# OSCILLAR_HFB_V1p0_AGSB.net
KiCad netlist of a schematic drawn in Altium Designer
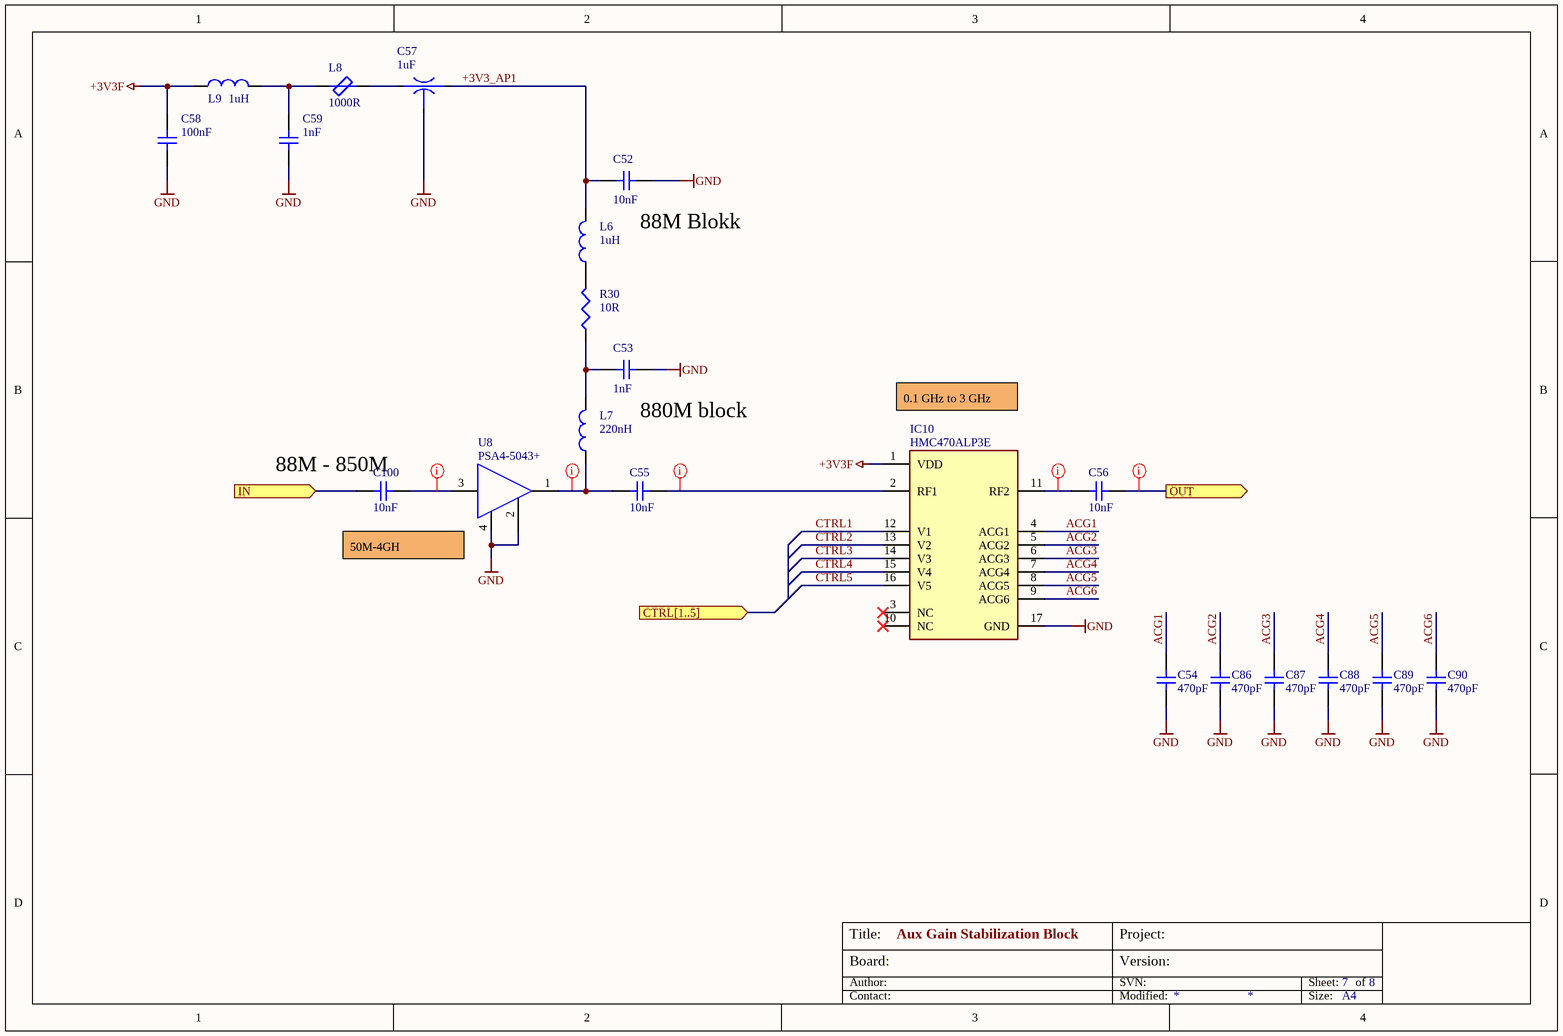
[diagram p0: OSCILLAR_HFB_V1p0_AGSB.SchDoc]

(export (version "E")
  (design (tool "Eeschema 10.0.6"))
  (components
    (comp (ref "C52")
      (value "10nF")
      (footprint "CAP-0805")
      (description "MLCC capacitor")
      (libsource (lib "SCHLIB") (part "NP-CAPACITOR"))
    )
    (comp (ref "C53")
      (value "1nF")
      (footprint "CAP-0805")
      (description "MLCC capacitor")
      (libsource (lib "SCHLIB") (part "NP-CAPACITOR"))
    )
    (comp (ref "C54")
      (value "470pF")
      (footprint "CAP_0603")
      (description "MLCC capacitor")
      (libsource (lib "SCHLIB") (part "NP-CAPACITOR"))
    )
    (comp (ref "C55")
      (value "10nF")
      (footprint "CAP_0603")
      (description "MLCC capacitor")
      (libsource (lib "SCHLIB") (part "NP-CAPACITOR"))
    )
    (comp (ref "C56")
      (value "10nF")
      (footprint "CAP_0603")
      (description "MLCC capacitor")
      (libsource (lib "SCHLIB") (part "NP-CAPACITOR"))
    )
    (comp (ref "C57")
      (value "1uF")
      (footprint "CAP-0805-EMI")
      (description "EMI filter capacitor")
      (libsource (lib "SCHLIB") (part "EMI_CAPACITOR"))
    )
    (comp (ref "C58")
      (value "100nF")
      (footprint "CAP-0805")
      (description "MLCC capacitor")
      (libsource (lib "SCHLIB") (part "NP-CAPACITOR"))
    )
    (comp (ref "C59")
      (value "1nF")
      (footprint "CAP-0805")
      (description "MLCC capacitor")
      (libsource (lib "SCHLIB") (part "NP-CAPACITOR"))
    )
    (comp (ref "C86")
      (value "470pF")
      (footprint "CAP_0603")
      (description "MLCC capacitor")
      (libsource (lib "SCHLIB") (part "NP-CAPACITOR"))
    )
    (comp (ref "C87")
      (value "470pF")
      (footprint "CAP_0603")
      (description "MLCC capacitor")
      (libsource (lib "SCHLIB") (part "NP-CAPACITOR"))
    )
    (comp (ref "C88")
      (value "470pF")
      (footprint "CAP_0603")
      (description "MLCC capacitor")
      (libsource (lib "SCHLIB") (part "NP-CAPACITOR"))
    )
    (comp (ref "C89")
      (value "470pF")
      (footprint "CAP_0603")
      (description "MLCC capacitor")
      (libsource (lib "SCHLIB") (part "NP-CAPACITOR"))
    )
    (comp (ref "C90")
      (value "470pF")
      (footprint "CAP_0603")
      (description "MLCC capacitor")
      (libsource (lib "SCHLIB") (part "NP-CAPACITOR"))
    )
    (comp (ref "C100")
      (value "10nF")
      (footprint "CAP_0603")
      (description "MLCC capacitor")
      (libsource (lib "SCHLIB") (part "NP-CAPACITOR"))
    )
    (comp (ref "IC10")
      (value "HMC470ALP3E")
      (footprint "QFN-16")
      (description "Attenuators 0.1 GHz to 3 GHz,1 dB LSB, 5-Bit, GaAs Digital Attenuator")
      (fields (field (name "PART NUMBER") "584-HMC470ALP3E"))
      (libsource (lib "SCHLIB") (part "HMC470ALP3E"))
    )
    (comp (ref "L6")
      (value "1uH")
      (footprint "IND-0805")
      (description "Air core coil")
      (libsource (lib "SCHLIB") (part "AC-INDUCTOR"))
    )
    (comp (ref "L7")
      (value "220nH")
      (footprint "IND-0805")
      (description "Air core coil")
      (libsource (lib "SCHLIB") (part "AC-INDUCTOR"))
    )
    (comp (ref "L8")
      (value "1000R")
      (footprint "IND-0805-EMI")
      (description "Chip Ferrite Bead, 1000R @100MHz, 1.6A")
      (fields (field (name "PART NUMBER") "81-BLM21SP102SN1D"))
      (libsource (lib "SCHLIB") (part "BLM21SP102SN1D"))
    )
    (comp (ref "L9")
      (value "1uH")
      (footprint "IND-0805-EMI")
      (description "Air core coil")
      (libsource (lib "SCHLIB") (part "AC-INDUCTOR"))
    )
    (comp (ref "R30")
      (value "10R")
      (footprint "RES-0805")
      (description "Metal Film Resistor")
      (libsource (lib "SCHLIB") (part "RESISTOR"))
    )
    (comp (ref "U8")
      (value "PSA4-5043+")
      (footprint "SOT-343-4")
      (description "RF Amplifier, Low noise, 50M-4GHz, +5V, +20dB")
      (fields (field (name "PART NUMBER") "139-PSA4-5043"))
      (libsource (lib "SCHLIB") (part "PSA4-5043+"))
    )
  )
  (nets
    (net (code "1") (name "+3V3F") (class "Default")
      (node (ref "C58") (pin "1") (pinfunction "1_1") (pintype "passive"))
      (node (ref "IC10") (pin "1") (pinfunction "VDD_1") (pintype "passive"))
      (node (ref "L9") (pin "1") (pinfunction "1_1") (pintype "passive"))
    )
    (net (code "2") (name "/+3V3_AP1") (class "Default")
      (node (ref "C52") (pin "1") (pinfunction "1_1") (pintype "passive"))
      (node (ref "C57") (pin "1") (pinfunction "1_1") (pintype "passive"))
      (node (ref "L6") (pin "2") (pinfunction "2_2") (pintype "passive"))
    )
    (net (code "3") (name "/ACG1") (class "Default")
      (node (ref "C54") (pin "1") (pinfunction "1_1") (pintype "passive"))
      (node (ref "IC10") (pin "4") (pinfunction "ACG1_4") (pintype "passive"))
    )
    (net (code "4") (name "/ACG2") (class "Default")
      (node (ref "C86") (pin "1") (pinfunction "1_1") (pintype "passive"))
      (node (ref "IC10") (pin "5") (pinfunction "ACG2_5") (pintype "passive"))
    )
    (net (code "5") (name "/ACG3") (class "Default")
      (node (ref "C87") (pin "1") (pinfunction "1_1") (pintype "passive"))
      (node (ref "IC10") (pin "6") (pinfunction "ACG3_6") (pintype "passive"))
    )
    (net (code "6") (name "/ACG4") (class "Default")
      (node (ref "C88") (pin "1") (pinfunction "1_1") (pintype "passive"))
      (node (ref "IC10") (pin "7") (pinfunction "ACG4_7") (pintype "passive"))
    )
    (net (code "7") (name "/ACG5") (class "Default")
      (node (ref "C89") (pin "1") (pinfunction "1_1") (pintype "passive"))
      (node (ref "IC10") (pin "8") (pinfunction "ACG5_8") (pintype "passive"))
    )
    (net (code "8") (name "/ACG6") (class "Default")
      (node (ref "C90") (pin "1") (pinfunction "1_1") (pintype "passive"))
      (node (ref "IC10") (pin "9") (pinfunction "ACG6_9") (pintype "passive"))
    )
    (net (code "9") (name "/CTRL1") (class "Default")
      (node (ref "IC10") (pin "12") (pinfunction "V1_12") (pintype "passive"))
    )
    (net (code "10") (name "/CTRL2") (class "Default")
      (node (ref "IC10") (pin "13") (pinfunction "V2_13") (pintype "passive"))
    )
    (net (code "11") (name "/CTRL3") (class "Default")
      (node (ref "IC10") (pin "14") (pinfunction "V3_14") (pintype "passive"))
    )
    (net (code "12") (name "/CTRL4") (class "Default")
      (node (ref "IC10") (pin "15") (pinfunction "V4_15") (pintype "passive"))
    )
    (net (code "13") (name "/CTRL5") (class "Default")
      (node (ref "IC10") (pin "16") (pinfunction "V5_16") (pintype "passive"))
    )
    (net (code "15") (name "/IN") (class "Default")
      (node (ref "C100") (pin "2") (pinfunction "2_2") (pintype "passive"))
    )
    (net (code "16") (name "/OUT") (class "Default")
      (node (ref "C56") (pin "1") (pinfunction "1_1") (pintype "passive"))
    )
    (net (code "17") (name "GND") (class "Default")
      (node (ref "C52") (pin "2") (pinfunction "2_2") (pintype "passive"))
      (node (ref "C53") (pin "2") (pinfunction "2_2") (pintype "passive"))
      (node (ref "C54") (pin "2") (pinfunction "2_2") (pintype "passive"))
      (node (ref "C57") (pin "2") (pinfunction "2_2") (pintype "passive"))
      (node (ref "C58") (pin "2") (pinfunction "2_2") (pintype "passive"))
      (node (ref "C59") (pin "2") (pinfunction "2_2") (pintype "passive"))
      (node (ref "C86") (pin "2") (pinfunction "2_2") (pintype "passive"))
      (node (ref "C87") (pin "2") (pinfunction "2_2") (pintype "passive"))
      (node (ref "C88") (pin "2") (pinfunction "2_2") (pintype "passive"))
      (node (ref "C89") (pin "2") (pinfunction "2_2") (pintype "passive"))
      (node (ref "C90") (pin "2") (pinfunction "2_2") (pintype "passive"))
      (node (ref "IC10") (pin "17") (pinfunction "GND_17") (pintype "passive"))
      (node (ref "U8") (pin "2") (pinfunction "GND_2") (pintype "passive"))
      (node (ref "U8") (pin "4") (pinfunction "4_4") (pintype "passive"))
    )
    (net (code "18") (name "Net-(C53-Pad1)") (class "Default")
      (node (ref "C53") (pin "1") (pinfunction "1_1") (pintype "passive"))
      (node (ref "L7") (pin "2") (pinfunction "2_2") (pintype "passive"))
      (node (ref "R30") (pin "1") (pintype "passive"))
    )
    (net (code "19") (name "Net-(C57-Pad3)") (class "Default")
      (node (ref "C57") (pin "3") (pinfunction "3_3") (pintype "passive"))
      (node (ref "L8") (pin "2") (pinfunction "2_2") (pintype "passive"))
    )
    (net (code "20") (name "Net-(C59-Pad1)") (class "Default")
      (node (ref "C59") (pin "1") (pinfunction "1_1") (pintype "passive"))
      (node (ref "L8") (pin "1") (pinfunction "1_1") (pintype "passive"))
      (node (ref "L9") (pin "2") (pinfunction "2_2") (pintype "passive"))
    )
    (net (code "21") (name "Net-(IC10-RF1)") (class "Default")
      (node (ref "C55") (pin "1") (pinfunction "1_1") (pintype "passive"))
      (node (ref "IC10") (pin "2") (pinfunction "RF1_2") (pintype "passive"))
    )
    (net (code "22") (name "Net-(IC10-RF2)") (class "Default")
      (node (ref "C56") (pin "2") (pinfunction "2_2") (pintype "passive"))
      (node (ref "IC10") (pin "11") (pinfunction "RF2_11") (pintype "passive"))
    )
    (net (code "23") (name "Net-(L6-Pad1)") (class "Default")
      (node (ref "L6") (pin "1") (pinfunction "1_1") (pintype "passive"))
      (node (ref "R30") (pin "2") (pintype "passive"))
    )
    (net (code "24") (name "Net-(U8-RF_IN)") (class "Default")
      (node (ref "C100") (pin "1") (pinfunction "1_1") (pintype "passive"))
      (node (ref "U8") (pin "3") (pinfunction "RF_IN_3") (pintype "passive"))
    )
    (net (code "25") (name "Net-(U8-RF_OUT)") (class "Default")
      (node (ref "C55") (pin "2") (pinfunction "2_2") (pintype "passive"))
      (node (ref "L7") (pin "1") (pinfunction "1_1") (pintype "passive"))
      (node (ref "U8") (pin "1") (pinfunction "RF_OUT_1") (pintype "passive"))
    )
    (net (code "26") (name "unconnected-(IC10-NC-Pad3)") (class "Default")
      (node (ref "IC10") (pin "3") (pinfunction "NC_3") (pintype "passive+no_connect"))
    )
    (net (code "27") (name "unconnected-(IC10-NC-Pad10)") (class "Default")
      (node (ref "IC10") (pin "10") (pinfunction "NC_10") (pintype "passive+no_connect"))
    )
  )
)
